# Trinket_Altium.net
KiCad netlist of a schematic drawn in Altium Designer
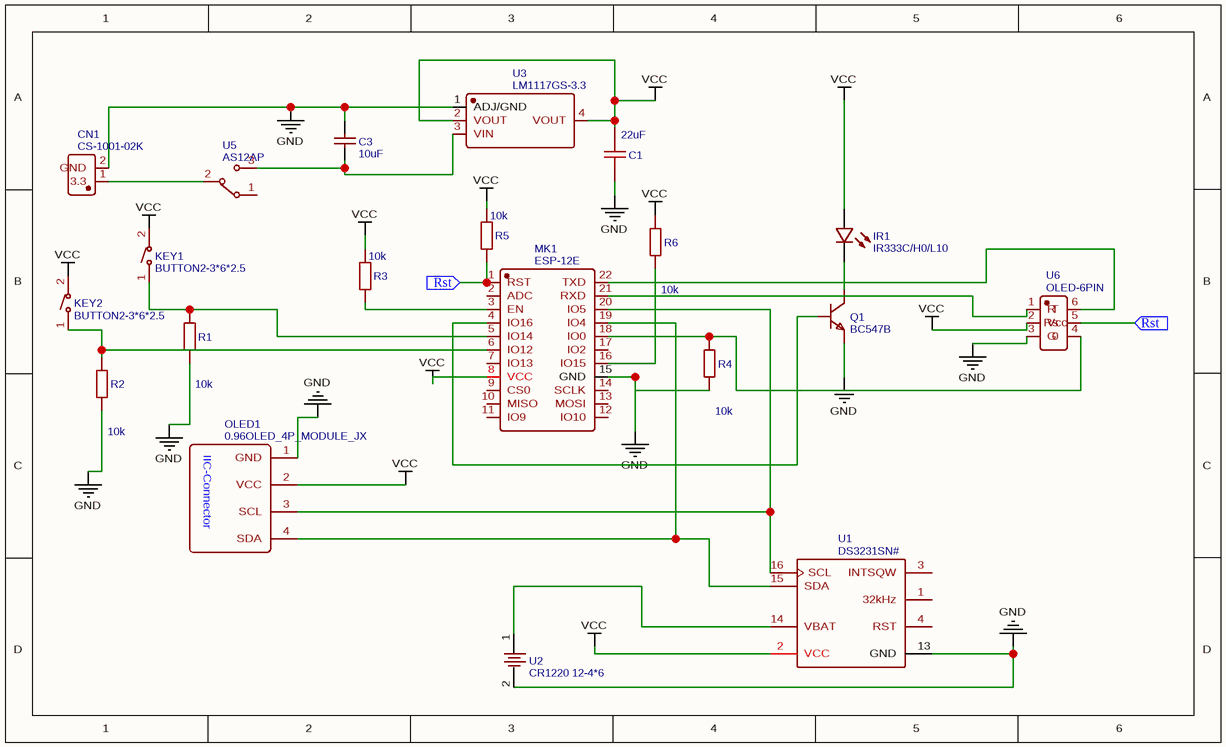
[diagram p0: Trinket_Altium.schdoc]

(export (version "E")
  (design (tool "Eeschema 10.0.6"))
  (components
    (comp (ref "C1")
      (value "22uF")
      (fields
        (field (name "MANUFACTURER") "YAGEO")
        (field (name "MANUFACTURER PART") "CC0805KKX5R5BB226")
        (field (name "CONTRIBUTOR") "LCSC")
      )
      (libsource (lib "altium-import") (part "root_0_22uF_"))
    )
    (comp (ref "C3")
      (value "10uF")
      (fields
        (field (name "MANUFACTURER") "YAGEO")
        (field (name "MANUFACTURER PART") "CC1206KKX5R8BB106")
        (field (name "CONTRIBUTOR") "LCSC")
      )
      (libsource (lib "altium-import") (part "root_1_10uF_"))
    )
    (comp (ref "CN1")
      (value "CS-1001-02K")
      (fields (field (name "MANUFACTURER") "CST(永丰盈)") (field (name "CONTRIBUTOR") "LCSC"))
      (libsource (lib "altium-import") (part "root_2_CS-1001-02K_"))
    )
    (comp (ref "IR1")
      (value "IR333C/H0/L10")
      (fields (field (name "MANUFACTURER") "EVERLIGHT"))
      (libsource (lib "altium-import") (part "root_3_IR333C/H0/L10_"))
    )
    (comp (ref "KEY1")
      (value "BUTTON2-3*6*2.5")
      (fields (field (name "CONTRIBUTOR") "LCSC"))
      (libsource (lib "altium-import") (part "root_1_BUTTON2-3*6*2.5_"))
    )
    (comp (ref "KEY2")
      (value "BUTTON2-3*6*2.5")
      (fields (field (name "CONTRIBUTOR") "LCSC"))
      (libsource (lib "altium-import") (part "root_1_BUTTON2-3*6*2.5_"))
    )
    (comp (ref "MK1")
      (value "ESP-12E")
      (fields (field (name "MANUFACTURER") "Ai-Thinker"))
      (libsource (lib "altium-import") (part "root_0_ESP-12E_"))
    )
    (comp (ref "OLED1")
      (value "0.96OLED_4P_MODULE_JX")
      (fields (field (name "CONTRIBUTOR") "LCSC"))
      (libsource (lib "altium-import") (part "root_0_0.96OLED_4P_MODULE_JX_"))
    )
    (comp (ref "Q1")
      (value "BC547B")
      (fields (field (name "MANUFACTURER") "LGE") (field (name "CONTRIBUTOR") "LCSC"))
      (libsource (lib "altium-import") (part "root_0_BC547B_"))
    )
    (comp (ref "R1")
      (value "10k")
      (fields
        (field (name "MANUFACTURER") "ResistorToday")
        (field (name "MANUFACTURER PART") "AECR1206F2R00T9")
        (field (name "CONTRIBUTOR") "LCSC")
      )
      (libsource (lib "altium-import") (part "root_1_10k_"))
    )
    (comp (ref "R2")
      (value "10k")
      (fields
        (field (name "MANUFACTURER") "ResistorToday")
        (field (name "MANUFACTURER PART") "AECR1206F2R00T9")
        (field (name "CONTRIBUTOR") "LCSC")
      )
      (libsource (lib "altium-import") (part "root_1_10k_"))
    )
    (comp (ref "R3")
      (value "10k")
      (fields
        (field (name "MANUFACTURER") "ResistorToday")
        (field (name "MANUFACTURER PART") "AECR1206F2R00T9")
        (field (name "CONTRIBUTOR") "LCSC")
      )
      (libsource (lib "altium-import") (part "root_1_10k_"))
    )
    (comp (ref "R4")
      (value "10k")
      (fields
        (field (name "MANUFACTURER") "ResistorToday")
        (field (name "MANUFACTURER PART") "AECR1206F2R00T9")
        (field (name "CONTRIBUTOR") "LCSC")
      )
      (libsource (lib "altium-import") (part "root_1_10k_"))
    )
    (comp (ref "R5")
      (value "10k")
      (fields
        (field (name "MANUFACTURER") "ResistorToday")
        (field (name "MANUFACTURER PART") "AECR1206F2R00T9")
        (field (name "CONTRIBUTOR") "LCSC")
      )
      (libsource (lib "altium-import") (part "root_1_10k_"))
    )
    (comp (ref "R6")
      (value "10k")
      (fields
        (field (name "MANUFACTURER") "ResistorToday")
        (field (name "MANUFACTURER PART") "AECR1206F2R00T9")
        (field (name "CONTRIBUTOR") "LCSC")
      )
      (libsource (lib "altium-import") (part "root_1_10k_"))
    )
    (comp (ref "U1")
      (value "DS3231SN#")
      (fields
        (field (name "MANUFACTURER") "MAXIM")
        (field (name "MANUFACTURER PART") "DS3231SN")
        (field (name "SUBPART_NO") "1")
      )
      (libsource (lib "altium-import") (part "root_0_DS3231SN#_"))
    )
    (comp (ref "U2")
      (value "CR1220 12-4*6")
      (fields (field (name "MANUFACTURER") "Q&J") (field (name "CONTRIBUTOR") "LCSC"))
      (libsource (lib "altium-import") (part "root_3_CR1220 12-4*6_"))
    )
    (comp (ref "U3")
      (value "LM1117GS-3.3")
      (fields (field (name "MANUFACTURER") "HTC Korea TAEJIN Tech") (field (name "CONTRIBUTOR") "LCSC"))
      (libsource (lib "altium-import") (part "root_0_LM1117GS-3.3_"))
    )
    (comp (ref "U5")
      (value "AS12AP")
      (fields (field (name "MANUFACTURER") "NKK Switches") (field (name "CONTRIBUTOR") "lcsc"))
      (libsource (lib "altium-import") (part "root_1_AS12AP_"))
    )
    (comp (ref "U6")
      (value "OLED-6PIN")
      (fields (field (name "CONTRIBUTOR") "lcsc"))
      (libsource (lib "altium-import") (part "root_0_OLED-6PIN_"))
    )
  )
  (nets
    (net (code "1") (name "/Rst") (class "Default")
      (node (ref "MK1") (pin "1") (pinfunction "RST_1") (pintype "passive"))
      (node (ref "R5") (pin "1") (pinfunction "1_1") (pintype "passive"))
      (node (ref "U6") (pin "5") (pinfunction "Rs_5") (pintype "passive"))
    )
    (net (code "2") (name "GND") (class "Default")
      (node (ref "C1") (pin "1") (pinfunction "1_1") (pintype "passive"))
      (node (ref "C3") (pin "2") (pinfunction "2_2") (pintype "passive"))
      (node (ref "CN1") (pin "2") (pinfunction "GND_2") (pintype "passive"))
      (node (ref "MK1") (pin "15") (pinfunction "GND_15") (pintype "passive"))
      (node (ref "OLED1") (pin "1") (pinfunction "GND_1") (pintype "passive"))
      (node (ref "Q1") (pin "3") (pinfunction "E_3") (pintype "passive"))
      (node (ref "R1") (pin "1") (pinfunction "1_1") (pintype "passive"))
      (node (ref "R2") (pin "1") (pinfunction "1_1") (pintype "passive"))
      (node (ref "R4") (pin "1") (pinfunction "1_1") (pintype "passive"))
      (node (ref "U1") (pin "13") (pinfunction "GND_13") (pintype "passive"))
      (node (ref "U2") (pin "2") (pinfunction "2_2") (pintype "passive"))
      (node (ref "U3") (pin "1") (pinfunction "ADJ/GND_1") (pintype "passive"))
      (node (ref "U6") (pin "3") (pinfunction "G_3") (pintype "passive"))
    )
    (net (code "3") (name "Net-(CN1-3.3)") (class "Default")
      (node (ref "CN1") (pin "1") (pinfunction "3.3_1") (pintype "passive"))
      (node (ref "U5") (pin "2") (pinfunction "2_2") (pintype "passive"))
    )
    (net (code "4") (name "Net-(IR1-C)") (class "Default")
      (node (ref "IR1") (pin "2") (pinfunction "C_2") (pintype "passive"))
      (node (ref "Q1") (pin "1") (pinfunction "C_1") (pintype "passive"))
    )
    (net (code "5") (name "Net-(MK1-EN)") (class "Default")
      (node (ref "MK1") (pin "3") (pinfunction "EN_3") (pintype "passive"))
      (node (ref "R3") (pin "1") (pinfunction "1_1") (pintype "passive"))
    )
    (net (code "6") (name "Net-(MK1-IO0)") (class "Default")
      (node (ref "MK1") (pin "18") (pinfunction "IO0_18") (pintype "passive"))
      (node (ref "R4") (pin "2") (pinfunction "2_2") (pintype "passive"))
      (node (ref "U6") (pin "4") (pinfunction "0_4") (pintype "passive"))
    )
    (net (code "7") (name "Net-(MK1-IO4)") (class "Default")
      (node (ref "MK1") (pin "19") (pinfunction "IO4_19") (pintype "passive"))
      (node (ref "OLED1") (pin "4") (pinfunction "SDA_4") (pintype "passive"))
      (node (ref "U1") (pin "15") (pinfunction "SDA_15") (pintype "passive"))
    )
    (net (code "8") (name "Net-(MK1-IO5)") (class "Default")
      (node (ref "MK1") (pin "20") (pinfunction "IO5_20") (pintype "passive"))
      (node (ref "OLED1") (pin "3") (pinfunction "SCL_3") (pintype "passive"))
      (node (ref "U1") (pin "16") (pinfunction "SCL_16") (pintype "passive"))
    )
    (net (code "9") (name "Net-(MK1-IO12)") (class "Default")
      (node (ref "KEY2") (pin "1") (pinfunction "1_1") (pintype "passive"))
      (node (ref "MK1") (pin "6") (pinfunction "IO12_6") (pintype "passive"))
      (node (ref "R2") (pin "2") (pinfunction "2_2") (pintype "passive"))
    )
    (net (code "10") (name "Net-(MK1-IO14)") (class "Default")
      (node (ref "KEY1") (pin "1") (pinfunction "1_1") (pintype "passive"))
      (node (ref "MK1") (pin "5") (pinfunction "IO14_5") (pintype "passive"))
      (node (ref "R1") (pin "2") (pinfunction "2_2") (pintype "passive"))
    )
    (net (code "11") (name "Net-(MK1-IO15)") (class "Default")
      (node (ref "MK1") (pin "16") (pinfunction "IO15_16") (pintype "passive"))
      (node (ref "R6") (pin "1") (pinfunction "1_1") (pintype "passive"))
    )
    (net (code "12") (name "Net-(MK1-IO16)") (class "Default")
      (node (ref "MK1") (pin "4") (pinfunction "IO16_4") (pintype "passive"))
      (node (ref "Q1") (pin "2") (pinfunction "B_2") (pintype "passive"))
    )
    (net (code "13") (name "Net-(MK1-RXD)") (class "Default")
      (node (ref "MK1") (pin "21") (pinfunction "RXD_21") (pintype "passive"))
      (node (ref "U6") (pin "1") (pinfunction "R_1") (pintype "passive"))
    )
    (net (code "14") (name "Net-(MK1-TXD)") (class "Default")
      (node (ref "MK1") (pin "22") (pinfunction "TXD_22") (pintype "passive"))
      (node (ref "U6") (pin "6") (pinfunction "T_6") (pintype "passive"))
    )
    (net (code "15") (name "Net-(U1-VBAT)") (class "Default")
      (node (ref "U1") (pin "14") (pinfunction "VBAT_14") (pintype "passive"))
      (node (ref "U2") (pin "1") (pinfunction "1_1") (pintype "passive"))
    )
    (net (code "16") (name "Net-(U3-VIN)") (class "Default")
      (node (ref "C3") (pin "1") (pinfunction "1_1") (pintype "passive"))
      (node (ref "U3") (pin "3") (pinfunction "VIN_3") (pintype "passive"))
      (node (ref "U5") (pin "3") (pinfunction "3_3") (pintype "passive"))
    )
    (net (code "17") (name "VCC") (class "Default")
      (node (ref "C1") (pin "2") (pinfunction "2_2") (pintype "passive"))
      (node (ref "IR1") (pin "1") (pinfunction "A_1") (pintype "passive"))
      (node (ref "KEY1") (pin "2") (pinfunction "2_2") (pintype "passive"))
      (node (ref "KEY2") (pin "2") (pinfunction "2_2") (pintype "passive"))
      (node (ref "MK1") (pin "8") (pinfunction "VCC_8") (pintype "passive"))
      (node (ref "OLED1") (pin "2") (pinfunction "VCC_2") (pintype "passive"))
      (node (ref "R3") (pin "2") (pinfunction "2_2") (pintype "passive"))
      (node (ref "R5") (pin "2") (pinfunction "2_2") (pintype "passive"))
      (node (ref "R6") (pin "2") (pinfunction "2_2") (pintype "passive"))
      (node (ref "U1") (pin "2") (pinfunction "VCC_2") (pintype "passive"))
      (node (ref "U3") (pin "2") (pinfunction "VOUT_2") (pintype "passive"))
      (node (ref "U3") (pin "4") (pinfunction "VOUT_4") (pintype "passive"))
      (node (ref "U6") (pin "2") (pinfunction "Vcc_2") (pintype "passive"))
    )
    (net (code "18") (name "unconnected-(MK1-ADC-Pad2)") (class "Default")
      (node (ref "MK1") (pin "2") (pinfunction "ADC_2") (pintype "passive"))
    )
    (net (code "19") (name "unconnected-(MK1-CS0-Pad9)") (class "Default")
      (node (ref "MK1") (pin "9") (pinfunction "CS0_9") (pintype "passive"))
    )
    (net (code "20") (name "unconnected-(MK1-IO2-Pad17)") (class "Default")
      (node (ref "MK1") (pin "17") (pinfunction "IO2_17") (pintype "passive"))
    )
    (net (code "21") (name "unconnected-(MK1-IO9-Pad11)") (class "Default")
      (node (ref "MK1") (pin "11") (pinfunction "IO9_11") (pintype "passive"))
    )
    (net (code "22") (name "unconnected-(MK1-IO10-Pad12)") (class "Default")
      (node (ref "MK1") (pin "12") (pinfunction "IO10_12") (pintype "passive"))
    )
    (net (code "23") (name "unconnected-(MK1-IO13-Pad7)") (class "Default")
      (node (ref "MK1") (pin "7") (pinfunction "IO13_7") (pintype "passive"))
    )
    (net (code "24") (name "unconnected-(MK1-MISO-Pad10)") (class "Default")
      (node (ref "MK1") (pin "10") (pinfunction "MISO_10") (pintype "passive"))
    )
    (net (code "25") (name "unconnected-(MK1-MOSI-Pad13)") (class "Default")
      (node (ref "MK1") (pin "13") (pinfunction "MOSI_13") (pintype "passive"))
    )
    (net (code "26") (name "unconnected-(MK1-SCLK-Pad14)") (class "Default")
      (node (ref "MK1") (pin "14") (pinfunction "SCLK_14") (pintype "passive"))
    )
    (net (code "27") (name "unconnected-(U1-32kHz-Pad1)") (class "Default")
      (node (ref "U1") (pin "1") (pinfunction "32kHz_1") (pintype "passive"))
    )
    (net (code "28") (name "unconnected-(U1-INTSQW-Pad3)") (class "Default")
      (node (ref "U1") (pin "3") (pinfunction "INTSQW_3") (pintype "passive"))
    )
    (net (code "29") (name "unconnected-(U1-RST-Pad4)") (class "Default")
      (node (ref "U1") (pin "4") (pinfunction "RST_4") (pintype "passive"))
    )
    (net (code "30") (name "unconnected-(U5-Pad1)") (class "Default")
      (node (ref "U5") (pin "1") (pinfunction "1_1") (pintype "passive"))
    )
  )
)
